# RS422.net
KiCad netlist of a schematic drawn in Altium Designer
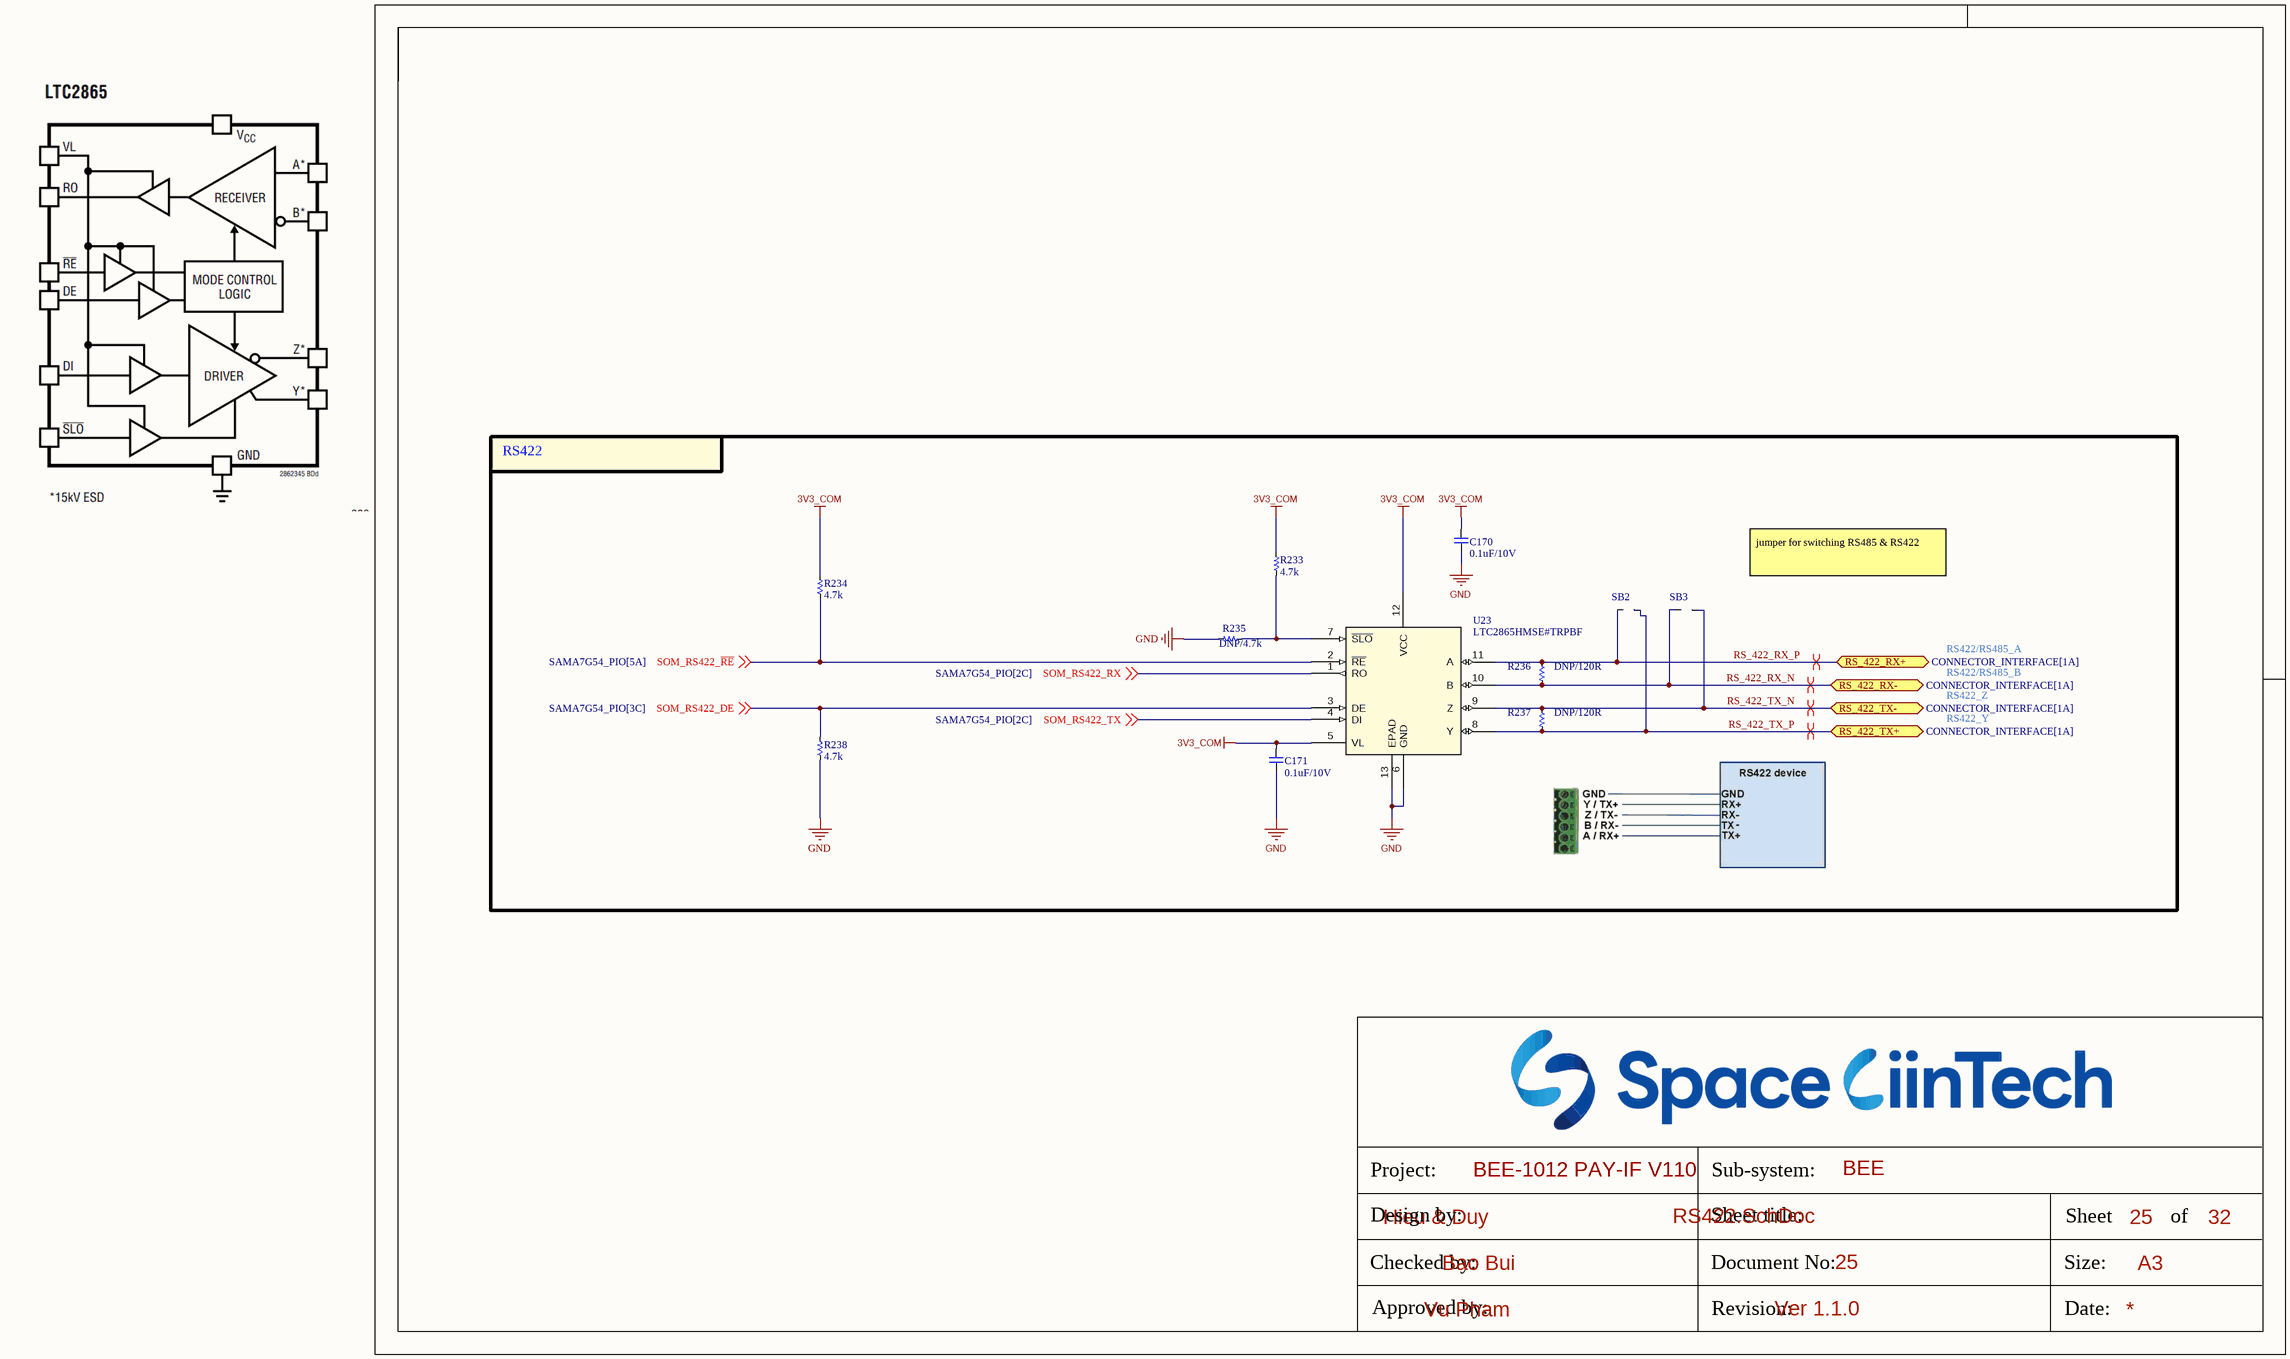
[diagram p0: RS422.SchDoc]

(export (version "E")
  (design (tool "Eeschema 10.0.6"))
  (components
    (comp (ref "C170")
      (value "0.1uF/10V")
      (footprint "CAP_C_1005X50_L")
      (description "CAP")
      (libsource (lib "LABLIB") (part "_CAP_C_2"))
    )
    (comp (ref "C171")
      (value "0.1uF/10V")
      (footprint "CAP_C_1005X50_L")
      (description "CAP")
      (libsource (lib "LABLIB") (part "_CAP_C_2"))
    )
    (comp (ref "R233")
      (value "4.7k")
      (footprint "RES_C_1005x30_L")
      (description "RES")
      (libsource (lib "IFBschelib") (part "_RES_B_2"))
    )
    (comp (ref "R234")
      (value "4.7k")
      (footprint "RES_C_1005x30_L")
      (description "RES")
      (libsource (lib "IFBschelib") (part "_RES_B_2"))
    )
    (comp (ref "R235")
      (value "DNP/4.7k")
      (footprint "RES_C_1005x30_L")
      (description "RES")
      (libsource (lib "IFBschelib") (part "_RES_B_2"))
    )
    (comp (ref "R236")
      (value "DNP/120R")
      (footprint "RES_C_1005x30_L")
      (description "RES")
      (libsource (lib "IFBschelib") (part "_RES_B_2"))
    )
    (comp (ref "R237")
      (value "DNP/120R")
      (footprint "RES_C_1005x30_L")
      (description "RES")
      (libsource (lib "IFBschelib") (part "_RES_B_2"))
    )
    (comp (ref "R238")
      (value "4.7k")
      (footprint "RES_C_1005x30_L")
      (description "RES")
      (libsource (lib "IFBschelib") (part "_RES_B_2"))
    )
    (comp (ref "SB2")
      (value "JUMPER")
      (footprint "JUMPER_1608")
      (libsource (lib "IFBschelib") (part "JUMPER"))
    )
    (comp (ref "SB3")
      (value "JUMPER")
      (footprint "JUMPER_1608")
      (libsource (lib "IFBschelib") (part "JUMPER"))
    )
    (comp (ref "U23")
      (value "LTC2865HMSE#TRPBF")
      (footprint "MSOP-12_MSE_LIT")
      (description "Â±60V Fault Protected 3V to 5.5V RS485/RS422 Transceivers")
      (fields (field (name "COPYRIGHT") "Copyright (C) 2025 Ultra Librarian. All rights reserved."))
      (libsource (lib "IFBschelib") (part "LTC2865HMSETRPBF"))
    )
  )
  (nets
    (net (code "1") (name "/RS_422_RX_N") (class "Default")
      (node (ref "R236") (pin "2") (pinfunction "2_2") (pintype "passive"))
      (node (ref "SB3") (pin "1") (pinfunction "1_1") (pintype "passive"))
      (node (ref "U23") (pin "10") (pinfunction "B_10") (pintype "bidirectional"))
    )
    (net (code "2") (name "/RS_422_RX_P") (class "Default")
      (node (ref "R236") (pin "1") (pinfunction "1_1") (pintype "passive"))
      (node (ref "SB2") (pin "1") (pinfunction "1_1") (pintype "passive"))
      (node (ref "U23") (pin "11") (pinfunction "A_11") (pintype "bidirectional"))
    )
    (net (code "3") (name "/RS_422_TX_N") (class "Default")
      (node (ref "R237") (pin "1") (pinfunction "1_1") (pintype "passive"))
      (node (ref "SB3") (pin "2") (pinfunction "2_2") (pintype "passive"))
      (node (ref "U23") (pin "9") (pinfunction "Z_9") (pintype "bidirectional"))
    )
    (net (code "4") (name "/RS_422_TX_P") (class "Default")
      (node (ref "R237") (pin "2") (pinfunction "2_2") (pintype "passive"))
      (node (ref "SB2") (pin "2") (pinfunction "2_2") (pintype "passive"))
      (node (ref "U23") (pin "8") (pinfunction "Y_8") (pintype "bidirectional"))
    )
    (net (code "5") (name "3V3_COM") (class "Default")
      (node (ref "C170") (pin "2") (pinfunction "2_2") (pintype "passive"))
      (node (ref "C171") (pin "2") (pinfunction "2_2") (pintype "passive"))
      (node (ref "R233") (pin "2") (pinfunction "2_2") (pintype "passive"))
      (node (ref "R234") (pin "2") (pinfunction "2_2") (pintype "passive"))
      (node (ref "U23") (pin "12") (pinfunction "VCC_12") (pintype "power_in"))
      (node (ref "U23") (pin "5") (pinfunction "VL_5") (pintype "power_in"))
    )
    (net (code "6") (name "GND") (class "Default")
      (node (ref "C170") (pin "1") (pinfunction "1_1") (pintype "passive"))
      (node (ref "C171") (pin "1") (pinfunction "1_1") (pintype "passive"))
      (node (ref "R235") (pin "2") (pinfunction "2_2") (pintype "passive"))
      (node (ref "R238") (pin "1") (pinfunction "1_1") (pintype "passive"))
      (node (ref "U23") (pin "13") (pinfunction "EPAD_13") (pintype "passive"))
      (node (ref "U23") (pin "6") (pinfunction "GND_6") (pintype "power_in"))
    )
    (net (code "7") (name "Net-(U23-~{SLO})") (class "Default")
      (node (ref "R233") (pin "1") (pinfunction "1_1") (pintype "passive"))
      (node (ref "R235") (pin "1") (pinfunction "1_1") (pintype "passive"))
      (node (ref "U23") (pin "7") (pinfunction "~{SLO}_7") (pintype "input"))
    )
    (net (code "8") (name "SOM_RS422_DE") (class "Default")
      (node (ref "R238") (pin "2") (pinfunction "2_2") (pintype "passive"))
      (node (ref "U23") (pin "3") (pinfunction "DE_3") (pintype "input"))
    )
    (net (code "9") (name "SOM_RS422_RX") (class "Default")
      (node (ref "U23") (pin "1") (pinfunction "RO_1") (pintype "output"))
    )
    (net (code "10") (name "SOM_RS422_TX") (class "Default")
      (node (ref "U23") (pin "4") (pinfunction "DI_4") (pintype "input"))
    )
    (net (code "11") (name "SOM_RS422_~{RE}") (class "Default")
      (node (ref "R234") (pin "1") (pinfunction "1_1") (pintype "passive"))
      (node (ref "U23") (pin "2") (pinfunction "~{RE}_2") (pintype "input"))
    )
  )
)
